# Power_Supply_2.net
KiCad netlist of a schematic drawn in Altium Designer
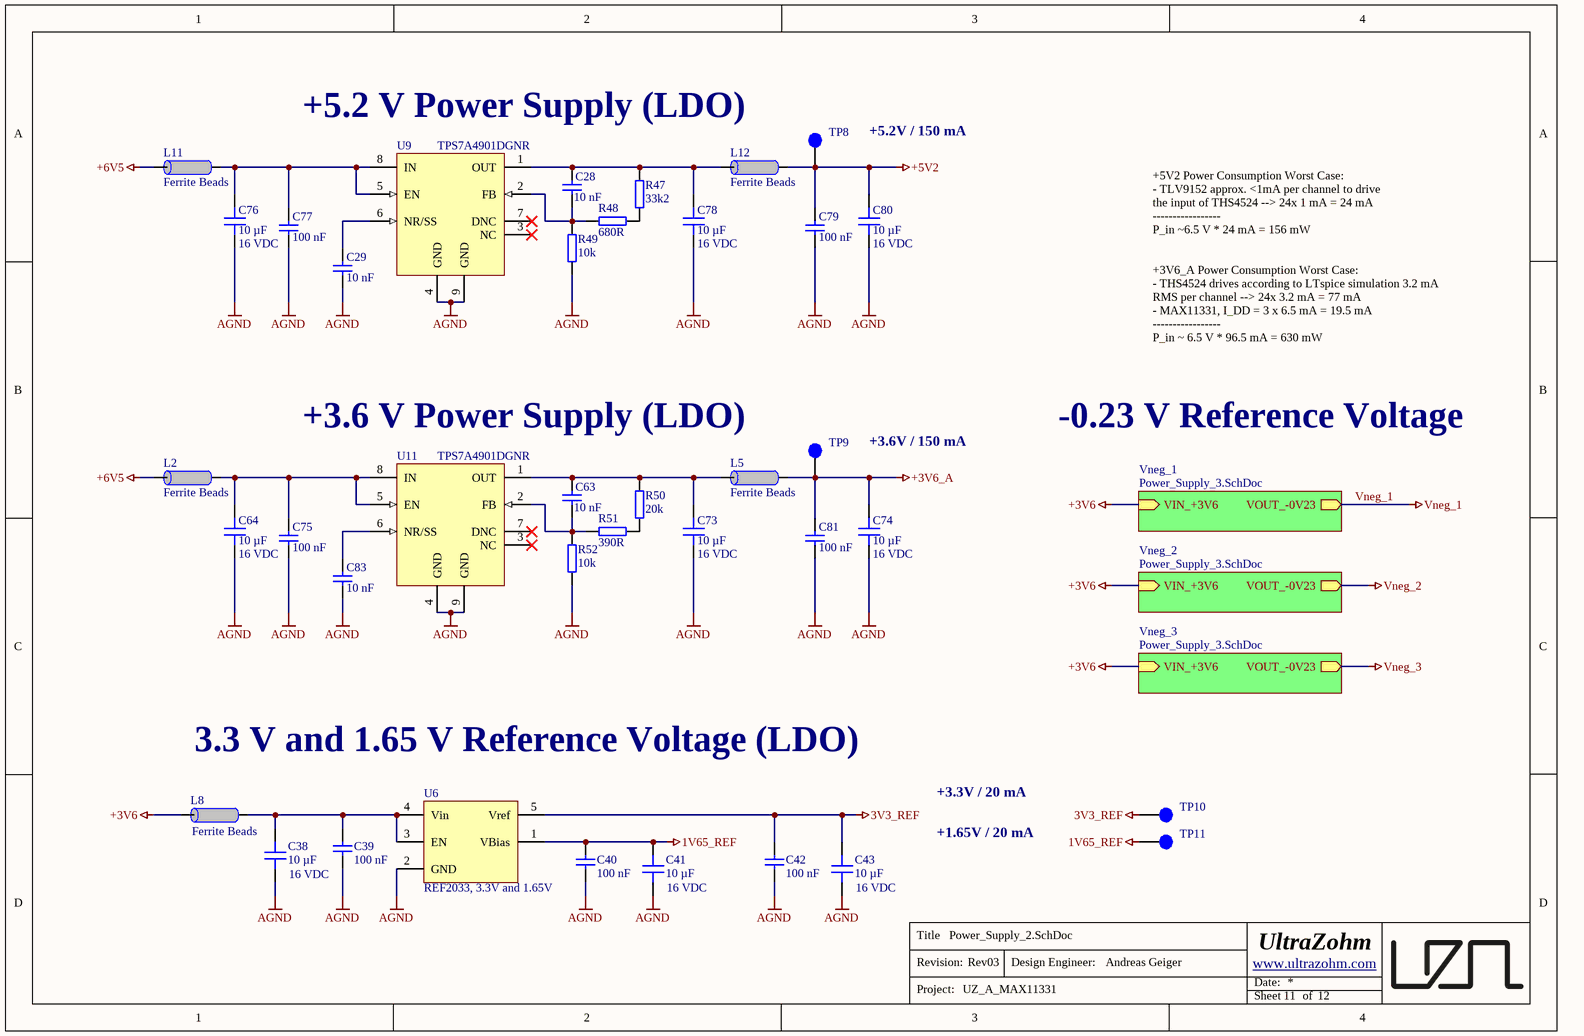
[diagram p0: Power_Supply_2.SchDoc]

(export (version "E")
  (design (tool "Eeschema 10.0.6"))
  (components
    (comp (ref "C28")
      (value "10 nF")
      (footprint "C_0402_TE")
      (description "Generic capacitor")
      (fields
        (field (name "MANUFACTURER PART NUMBER") "UZgen_C_0402_10nF_50V_NP0")
        (field (name "MANUFACTURER") "UZgen")
        (field (name "CREATED FROM") "UZgenTool")
      )
      (libsource (lib "user") (part "CAP-NP"))
    )
    (comp (ref "C29")
      (value "10 nF")
      (footprint "C_0402_TE")
      (description "Generic capacitor")
      (fields
        (field (name "MANUFACTURER PART NUMBER") "UZgen_C_0402_10nF_50V_NP0")
        (field (name "MANUFACTURER") "UZgen")
        (field (name "CREATED FROM") "UZgenTool")
      )
      (libsource (lib "user") (part "CAP-NP"))
    )
    (comp (ref "C38")
      (value "10 µF")
      (footprint "C_0603_TE")
      (description "Capacitor 0603, 16 VDC, 10 µF, X5R")
      (fields
        (field (name "MANUFACTURER PART NUMBER") "CL10A106MO8NQNC")
        (field (name "MANUFACTURER") "Samsung Electro-Mechanics")
        (field (name "VOLTAGE RATING") "16 VDC")
        (field (name "CREATED FROM") "AGeiger")
      )
      (libsource (lib "user") (part "Capacitor"))
    )
    (comp (ref "C39")
      (value "100 nF")
      (footprint "C_0603_TE")
      (description "Generic capacitor")
      (fields
        (field (name "MANUFACTURER PART NUMBER") "UZgen_C_0603_100nF_50V_X7R")
        (field (name "MANUFACTURER") "UZgen")
        (field (name "CREATED FROM") "AGeiger")
      )
      (libsource (lib "user") (part "CAP-NP"))
    )
    (comp (ref "C40")
      (value "100 nF")
      (footprint "C_0603_TE")
      (description "Generic capacitor")
      (fields
        (field (name "MANUFACTURER PART NUMBER") "UZgen_C_0603_100nF_50V_X7R")
        (field (name "MANUFACTURER") "UZgen")
        (field (name "CREATED FROM") "AGeiger")
      )
      (libsource (lib "user") (part "CAP-NP"))
    )
    (comp (ref "C41")
      (value "10 µF")
      (footprint "C_0603_TE")
      (description "Capacitor 0603, 16 VDC, 10 µF, X5R")
      (fields
        (field (name "MANUFACTURER PART NUMBER") "CL10A106MO8NQNC")
        (field (name "MANUFACTURER") "Samsung Electro-Mechanics")
        (field (name "VOLTAGE RATING") "16 VDC")
        (field (name "CREATED FROM") "AGeiger")
      )
      (libsource (lib "user") (part "Capacitor"))
    )
    (comp (ref "C42")
      (value "100 nF")
      (footprint "C_0603_TE")
      (description "Generic capacitor")
      (fields
        (field (name "MANUFACTURER PART NUMBER") "UZgen_C_0603_100nF_50V_X7R")
        (field (name "MANUFACTURER") "UZgen")
        (field (name "CREATED FROM") "AGeiger")
      )
      (libsource (lib "user") (part "CAP-NP"))
    )
    (comp (ref "C43")
      (value "10 µF")
      (footprint "C_0603_TE")
      (description "Capacitor 0603, 16 VDC, 10 µF, X5R")
      (fields
        (field (name "MANUFACTURER PART NUMBER") "CL10A106MO8NQNC")
        (field (name "MANUFACTURER") "Samsung Electro-Mechanics")
        (field (name "VOLTAGE RATING") "16 VDC")
        (field (name "CREATED FROM") "AGeiger")
      )
      (libsource (lib "user") (part "Capacitor"))
    )
    (comp (ref "C63")
      (value "10 nF")
      (footprint "C_0402_TE")
      (description "Generic capacitor")
      (fields
        (field (name "MANUFACTURER PART NUMBER") "UZgen_C_0402_10nF_50V_NP0")
        (field (name "MANUFACTURER") "UZgen")
        (field (name "CREATED FROM") "UZgenTool")
      )
      (libsource (lib "user") (part "CAP-NP"))
    )
    (comp (ref "C64")
      (value "10 µF")
      (footprint "C_0603_TE")
      (description "Capacitor 0603, 16 VDC, 10 µF, X5R")
      (fields
        (field (name "MANUFACTURER PART NUMBER") "CL10A106MO8NQNC")
        (field (name "MANUFACTURER") "Samsung Electro-Mechanics")
        (field (name "VOLTAGE RATING") "16 VDC")
        (field (name "CREATED FROM") "AGeiger")
      )
      (libsource (lib "user") (part "Capacitor"))
    )
    (comp (ref "C73")
      (value "10 µF")
      (footprint "C_0603_TE")
      (description "Capacitor 0603, 16 VDC, 10 µF, X5R")
      (fields
        (field (name "MANUFACTURER PART NUMBER") "CL10A106MO8NQNC")
        (field (name "MANUFACTURER") "Samsung Electro-Mechanics")
        (field (name "VOLTAGE RATING") "16 VDC")
        (field (name "CREATED FROM") "AGeiger")
      )
      (libsource (lib "user") (part "Capacitor"))
    )
    (comp (ref "C74")
      (value "10 µF")
      (footprint "C_0603_TE")
      (description "Capacitor 0603, 16 VDC, 10 µF, X5R")
      (fields
        (field (name "MANUFACTURER PART NUMBER") "CL10A106MO8NQNC")
        (field (name "MANUFACTURER") "Samsung Electro-Mechanics")
        (field (name "VOLTAGE RATING") "16 VDC")
        (field (name "CREATED FROM") "AGeiger")
      )
      (libsource (lib "user") (part "Capacitor"))
    )
    (comp (ref "C75")
      (value "100 nF")
      (footprint "C_0603_TE")
      (description "Generic capacitor")
      (fields
        (field (name "MANUFACTURER PART NUMBER") "UZgen_C_0603_100nF_50V_X7R")
        (field (name "MANUFACTURER") "UZgen")
        (field (name "CREATED FROM") "AGeiger")
      )
      (libsource (lib "user") (part "CAP-NP"))
    )
    (comp (ref "C76")
      (value "10 µF")
      (footprint "C_0603_TE")
      (description "Capacitor 0603, 16 VDC, 10 µF, X5R")
      (fields
        (field (name "MANUFACTURER PART NUMBER") "CL10A106MO8NQNC")
        (field (name "MANUFACTURER") "Samsung Electro-Mechanics")
        (field (name "VOLTAGE RATING") "16 VDC")
        (field (name "CREATED FROM") "AGeiger")
      )
      (libsource (lib "user") (part "Capacitor"))
    )
    (comp (ref "C77")
      (value "100 nF")
      (footprint "C_0603_TE")
      (description "Generic capacitor")
      (fields
        (field (name "MANUFACTURER PART NUMBER") "UZgen_C_0603_100nF_50V_X7R")
        (field (name "MANUFACTURER") "UZgen")
        (field (name "CREATED FROM") "AGeiger")
      )
      (libsource (lib "user") (part "CAP-NP"))
    )
    (comp (ref "C78")
      (value "10 µF")
      (footprint "C_0603_TE")
      (description "Capacitor 0603, 16 VDC, 10 µF, X5R")
      (fields
        (field (name "MANUFACTURER PART NUMBER") "CL10A106MO8NQNC")
        (field (name "MANUFACTURER") "Samsung Electro-Mechanics")
        (field (name "VOLTAGE RATING") "16 VDC")
        (field (name "CREATED FROM") "AGeiger")
      )
      (libsource (lib "user") (part "Capacitor"))
    )
    (comp (ref "C79")
      (value "100 nF")
      (footprint "C_0603_TE")
      (description "Generic capacitor")
      (fields
        (field (name "MANUFACTURER PART NUMBER") "UZgen_C_0603_100nF_50V_X7R")
        (field (name "MANUFACTURER") "UZgen")
        (field (name "CREATED FROM") "AGeiger")
      )
      (libsource (lib "user") (part "CAP-NP"))
    )
    (comp (ref "C80")
      (value "10 µF")
      (footprint "C_0603_TE")
      (description "Capacitor 0603, 16 VDC, 10 µF, X5R")
      (fields
        (field (name "MANUFACTURER PART NUMBER") "CL10A106MO8NQNC")
        (field (name "MANUFACTURER") "Samsung Electro-Mechanics")
        (field (name "VOLTAGE RATING") "16 VDC")
        (field (name "CREATED FROM") "AGeiger")
      )
      (libsource (lib "user") (part "Capacitor"))
    )
    (comp (ref "C81")
      (value "100 nF")
      (footprint "C_0603_TE")
      (description "Generic capacitor")
      (fields
        (field (name "MANUFACTURER PART NUMBER") "UZgen_C_0603_100nF_50V_X7R")
        (field (name "MANUFACTURER") "UZgen")
        (field (name "CREATED FROM") "AGeiger")
      )
      (libsource (lib "user") (part "CAP-NP"))
    )
    (comp (ref "C83")
      (value "10 nF")
      (footprint "C_0402_TE")
      (description "Generic capacitor")
      (fields
        (field (name "MANUFACTURER PART NUMBER") "UZgen_C_0402_10nF_50V_NP0")
        (field (name "MANUFACTURER") "UZgen")
        (field (name "CREATED FROM") "UZgenTool")
      )
      (libsource (lib "user") (part "CAP-NP"))
    )
    (comp (ref "L2")
      (value "UPZ2012E601-2R0TF")
      (footprint "INDC2012X92N_V")
      (description "2A 1 90mΩ 600Ω@100MHz ±25% 0805  Ferrite Beads ROHS")
      (fields
        (field (name "COMPONENT TYPE") "Ferrite Beads")
        (field (name "MANUFACTURER") "Sunlord")
        (field (name "LCSC PART NUMBER") "C98308")
        (field (name "CREATED FROM") "AGeiger")
      )
      (libsource (lib "user") (part "Ferrite_Bead"))
    )
    (comp (ref "L5")
      (value "UPZ2012E601-2R0TF")
      (footprint "INDC2012X92N_V")
      (description "2A 1 90mΩ 600Ω@100MHz ±25% 0805  Ferrite Beads ROHS")
      (fields
        (field (name "COMPONENT TYPE") "Ferrite Beads")
        (field (name "MANUFACTURER") "Sunlord")
        (field (name "LCSC PART NUMBER") "C98308")
        (field (name "CREATED FROM") "AGeiger")
      )
      (libsource (lib "user") (part "Ferrite_Bead"))
    )
    (comp (ref "L8")
      (value "UPZ2012E601-2R0TF")
      (footprint "INDC2012X92N_V")
      (description "2A 1 90mΩ 600Ω@100MHz ±25% 0805  Ferrite Beads ROHS")
      (fields
        (field (name "COMPONENT TYPE") "Ferrite Beads")
        (field (name "MANUFACTURER") "Sunlord")
        (field (name "LCSC PART NUMBER") "C98308")
        (field (name "CREATED FROM") "AGeiger")
      )
      (libsource (lib "user") (part "Ferrite_Bead"))
    )
    (comp (ref "L11")
      (value "UPZ2012E601-2R0TF")
      (footprint "INDC2012X92N_V")
      (description "2A 1 90mΩ 600Ω@100MHz ±25% 0805  Ferrite Beads ROHS")
      (fields
        (field (name "COMPONENT TYPE") "Ferrite Beads")
        (field (name "MANUFACTURER") "Sunlord")
        (field (name "LCSC PART NUMBER") "C98308")
        (field (name "CREATED FROM") "AGeiger")
      )
      (libsource (lib "user") (part "Ferrite_Bead"))
    )
    (comp (ref "L12")
      (value "UPZ2012E601-2R0TF")
      (footprint "INDC2012X92N_V")
      (description "2A 1 90mΩ 600Ω@100MHz ±25% 0805  Ferrite Beads ROHS")
      (fields
        (field (name "COMPONENT TYPE") "Ferrite Beads")
        (field (name "MANUFACTURER") "Sunlord")
        (field (name "LCSC PART NUMBER") "C98308")
        (field (name "CREATED FROM") "AGeiger")
      )
      (libsource (lib "user") (part "Ferrite_Bead"))
    )
    (comp (ref "R47")
      (value "33k2")
      (footprint "R_0402_TE")
      (description "62.5mW Thick Film Resistor 50V ±100ppm/℃ ±1% 33.2kΩ 0402 Chip Resistor - Surface Mount ROHS")
      (fields
        (field (name "TOLERANCE") "1%")
        (field (name "MANUFACTURER PART NUMBER") "0402WGF3322TCE")
        (field (name "CREATED FROM") "AGeiger")
      )
      (libsource (lib "user") (part "Resistor"))
    )
    (comp (ref "R48")
      (value "680R")
      (footprint "R_0402_TE")
      (description "Generic resistor")
      (fields
        (field (name "MANUFACTURER PART NUMBER") "UZgen_R_0402_680R")
        (field (name "MANUFACTURER") "UZgen")
        (field (name "CREATED FROM") "UZgenTool")
      )
      (libsource (lib "user") (part "RES"))
    )
    (comp (ref "R49")
      (value "10k")
      (footprint "R_0402_TE")
      (description "Generic resistor")
      (fields
        (field (name "MANUFACTURER PART NUMBER") "UZgen_R_0402_10k")
        (field (name "MANUFACTURER") "UZgen")
        (field (name "CREATED FROM") "UZgenTool")
      )
      (libsource (lib "user") (part "RES"))
    )
    (comp (ref "R50")
      (value "20k")
      (footprint "R_0402_TE")
      (description "Generic resistor")
      (fields
        (field (name "TOLERANCE") "1 %")
        (field (name "MANUFACTURER PART NUMBER") "UZgen_R_0402_20k")
        (field (name "CREATED FROM") "UZgenTool")
      )
      (libsource (lib "user") (part "RES"))
    )
    (comp (ref "R51")
      (value "390R")
      (footprint "R_0402_TE")
      (description "Generic resistor")
      (fields
        (field (name "MANUFACTURER PART NUMBER") "UZgen_R_0402_390R")
        (field (name "MANUFACTURER") "UZgen")
        (field (name "CREATED FROM") "UZgenTool")
      )
      (libsource (lib "user") (part "RES"))
    )
    (comp (ref "R52")
      (value "10k")
      (footprint "R_0402_TE")
      (description "Generic resistor")
      (fields
        (field (name "MANUFACTURER PART NUMBER") "UZgen_R_0402_10k")
        (field (name "MANUFACTURER") "UZgen")
        (field (name "CREATED FROM") "UZgenTool")
      )
      (libsource (lib "user") (part "RES"))
    )
    (comp (ref "TP8")
      (value "Testpoint 1mm")
      (footprint "TP_1mm")
      (fields
        (field (name "MANUFACTURER PART NUMBER") "Testpoint_1mm")
        (field (name "MANUFACTURER") "UltraZohm")
        (field (name "CREATED") "2018_06_25_AGeiger")
        (field (name "CREATED FROM") "AGeiger")
      )
      (libsource (lib "user") (part "TP_1mm"))
    )
    (comp (ref "TP9")
      (value "Testpoint 1mm")
      (footprint "TP_1mm")
      (fields
        (field (name "MANUFACTURER PART NUMBER") "Testpoint_1mm")
        (field (name "MANUFACTURER") "UltraZohm")
        (field (name "CREATED") "2018_06_25_AGeiger")
        (field (name "CREATED FROM") "AGeiger")
      )
      (libsource (lib "user") (part "TP_1mm"))
    )
    (comp (ref "TP10")
      (value "Testpoint 1mm")
      (footprint "TP_1mm")
      (fields
        (field (name "MANUFACTURER PART NUMBER") "Testpoint_1mm")
        (field (name "MANUFACTURER") "UltraZohm")
        (field (name "CREATED") "2018_06_25_AGeiger")
        (field (name "CREATED FROM") "AGeiger")
      )
      (libsource (lib "user") (part "TP_1mm"))
    )
    (comp (ref "TP11")
      (value "Testpoint 1mm")
      (footprint "TP_1mm")
      (fields
        (field (name "MANUFACTURER PART NUMBER") "Testpoint_1mm")
        (field (name "MANUFACTURER") "UltraZohm")
        (field (name "CREATED") "2018_06_25_AGeiger")
        (field (name "CREATED FROM") "AGeiger")
      )
      (libsource (lib "user") (part "TP_1mm"))
    )
    (comp (ref "U6")
      (value "REF2033, 3.3V and 1.65V")
      (footprint "SOT23-5_N")
      (description "REF20xx Low-Drift, Low-Power, Dual-Output, VREF and VREF / 2 Voltage References")
      (fields
        (field (name "MANUFACTURER PART NUMBER") "REF2033AIDDCT")
        (field (name "MANUFACTURER") "Texas Instruments")
        (field (name "CREATED FROM") "AGeiger")
      )
      (libsource (lib "user") (part "REF2033"))
    )
    (comp (ref "U9")
      (value "TPS7A4901DGNR")
      (footprint "SOP65P490X110-9N")
      (description "36 V, -150 mA, ultralow-noise, positive linear regulator")
      (fields
        (field (name "MANUFACTURER") "Texas Instruments")
        (field (name "LCSC PART NUMBER") "C16430")
        (field (name "CREATED FROM") "AGeiger")
      )
      (libsource (lib "user") (part "TPS7A4901"))
    )
    (comp (ref "U11")
      (value "TPS7A4901DGNR")
      (footprint "SOP65P490X110-9N")
      (description "36 V, -150 mA, ultralow-noise, positive linear regulator")
      (fields
        (field (name "MANUFACTURER") "Texas Instruments")
        (field (name "LCSC PART NUMBER") "C16430")
        (field (name "CREATED FROM") "AGeiger")
      )
      (libsource (lib "user") (part "TPS7A4901"))
    )
  )
  (nets
    (net (code "1") (name "+3V6") (class "Default")
      (node (ref "L8") (pin "2") (pinfunction "2_2") (pintype "passive"))
    )
    (net (code "2") (name "+3V6_A") (class "Default")
      (node (ref "C74") (pin "2") (pinfunction "2_2") (pintype "passive"))
      (node (ref "C81") (pin "2") (pinfunction "2_2") (pintype "passive"))
      (node (ref "L5") (pin "1") (pinfunction "1_1") (pintype "passive"))
      (node (ref "TP9") (pin "1") (pintype "passive"))
    )
    (net (code "3") (name "+5V2") (class "Default")
      (node (ref "C79") (pin "2") (pinfunction "2_2") (pintype "passive"))
      (node (ref "C80") (pin "2") (pinfunction "2_2") (pintype "passive"))
      (node (ref "L12") (pin "1") (pinfunction "1_1") (pintype "passive"))
      (node (ref "TP8") (pin "1") (pintype "passive"))
    )
    (net (code "4") (name "+6V5") (class "Default")
      (node (ref "L11") (pin "2") (pinfunction "2_2") (pintype "passive"))
      (node (ref "L2") (pin "2") (pinfunction "2_2") (pintype "passive"))
    )
    (net (code "5") (name "1V65_REF") (class "Default")
      (node (ref "C40") (pin "2") (pinfunction "2_2") (pintype "passive"))
      (node (ref "C41") (pin "2") (pinfunction "2_2") (pintype "passive"))
      (node (ref "TP11") (pin "1") (pintype "passive"))
      (node (ref "U6") (pin "1") (pinfunction "VBias_1") (pintype "passive"))
    )
    (net (code "6") (name "3V3_REF") (class "Default")
      (node (ref "C42") (pin "2") (pinfunction "2_2") (pintype "passive"))
      (node (ref "C43") (pin "2") (pinfunction "2_2") (pintype "passive"))
      (node (ref "TP10") (pin "1") (pintype "passive"))
      (node (ref "U6") (pin "5") (pinfunction "Vref_5") (pintype "passive"))
    )
    (net (code "7") (name "AGND") (class "Default")
      (node (ref "C29") (pin "1") (pinfunction "1_1") (pintype "passive"))
      (node (ref "C38") (pin "1") (pinfunction "1_1") (pintype "passive"))
      (node (ref "C39") (pin "1") (pinfunction "1_1") (pintype "passive"))
      (node (ref "C40") (pin "1") (pinfunction "1_1") (pintype "passive"))
      (node (ref "C41") (pin "1") (pinfunction "1_1") (pintype "passive"))
      (node (ref "C42") (pin "1") (pinfunction "1_1") (pintype "passive"))
      (node (ref "C43") (pin "1") (pinfunction "1_1") (pintype "passive"))
      (node (ref "C64") (pin "1") (pinfunction "1_1") (pintype "passive"))
      (node (ref "C73") (pin "1") (pinfunction "1_1") (pintype "passive"))
      (node (ref "C74") (pin "1") (pinfunction "1_1") (pintype "passive"))
      (node (ref "C75") (pin "1") (pinfunction "1_1") (pintype "passive"))
      (node (ref "C76") (pin "1") (pinfunction "1_1") (pintype "passive"))
      (node (ref "C77") (pin "1") (pinfunction "1_1") (pintype "passive"))
      (node (ref "C78") (pin "1") (pinfunction "1_1") (pintype "passive"))
      (node (ref "C79") (pin "1") (pinfunction "1_1") (pintype "passive"))
      (node (ref "C80") (pin "1") (pinfunction "1_1") (pintype "passive"))
      (node (ref "C81") (pin "1") (pinfunction "1_1") (pintype "passive"))
      (node (ref "C83") (pin "1") (pinfunction "1_1") (pintype "passive"))
      (node (ref "R49") (pin "1") (pinfunction "1_1") (pintype "passive"))
      (node (ref "R52") (pin "1") (pinfunction "1_1") (pintype "passive"))
      (node (ref "U11") (pin "4") (pinfunction "GND_4") (pintype "power_in"))
      (node (ref "U11") (pin "9") (pinfunction "GND_9") (pintype "power_in"))
      (node (ref "U6") (pin "2") (pinfunction "GND_2") (pintype "passive"))
      (node (ref "U9") (pin "4") (pinfunction "GND_4") (pintype "power_in"))
      (node (ref "U9") (pin "9") (pinfunction "GND_9") (pintype "power_in"))
    )
    (net (code "8") (name "Net-(R47-Pad1)") (class "Default")
      (node (ref "R47") (pin "1") (pinfunction "1_1") (pintype "passive"))
      (node (ref "R48") (pin "2") (pinfunction "2_2") (pintype "passive"))
    )
    (net (code "9") (name "Net-(R50-Pad1)") (class "Default")
      (node (ref "R50") (pin "1") (pinfunction "1_1") (pintype "passive"))
      (node (ref "R51") (pin "2") (pinfunction "2_2") (pintype "passive"))
    )
    (net (code "10") (name "Net-(U6-EN)") (class "Default")
      (node (ref "C38") (pin "2") (pinfunction "2_2") (pintype "passive"))
      (node (ref "C39") (pin "2") (pinfunction "2_2") (pintype "passive"))
      (node (ref "L8") (pin "1") (pinfunction "1_1") (pintype "passive"))
      (node (ref "U6") (pin "3") (pinfunction "EN_3") (pintype "passive"))
      (node (ref "U6") (pin "4") (pinfunction "Vin_4") (pintype "passive"))
    )
    (net (code "11") (name "Net-(U9-EN)") (class "Default")
      (node (ref "C76") (pin "2") (pinfunction "2_2") (pintype "passive"))
      (node (ref "C77") (pin "2") (pinfunction "2_2") (pintype "passive"))
      (node (ref "L11") (pin "1") (pinfunction "1_1") (pintype "passive"))
      (node (ref "U9") (pin "5") (pinfunction "EN_5") (pintype "input"))
      (node (ref "U9") (pin "8") (pinfunction "IN_8") (pintype "power_in"))
    )
    (net (code "12") (name "Net-(U9-FB)") (class "Default")
      (node (ref "C28") (pin "1") (pinfunction "1_1") (pintype "passive"))
      (node (ref "R48") (pin "1") (pinfunction "1_1") (pintype "passive"))
      (node (ref "R49") (pin "2") (pinfunction "2_2") (pintype "passive"))
      (node (ref "U9") (pin "2") (pinfunction "FB_2") (pintype "input"))
    )
    (net (code "13") (name "Net-(U9-NR{slash}SS)") (class "Default")
      (node (ref "C29") (pin "2") (pinfunction "2_2") (pintype "passive"))
      (node (ref "U9") (pin "6") (pinfunction "NR/SS_6") (pintype "input"))
    )
    (net (code "14") (name "Net-(U9-OUT)") (class "Default")
      (node (ref "C28") (pin "2") (pinfunction "2_2") (pintype "passive"))
      (node (ref "C78") (pin "2") (pinfunction "2_2") (pintype "passive"))
      (node (ref "L12") (pin "2") (pinfunction "2_2") (pintype "passive"))
      (node (ref "R47") (pin "2") (pinfunction "2_2") (pintype "passive"))
      (node (ref "U9") (pin "1") (pinfunction "OUT_1") (pintype "power_in"))
    )
    (net (code "15") (name "Net-(U11-EN)") (class "Default")
      (node (ref "C64") (pin "2") (pinfunction "2_2") (pintype "passive"))
      (node (ref "C75") (pin "2") (pinfunction "2_2") (pintype "passive"))
      (node (ref "L2") (pin "1") (pinfunction "1_1") (pintype "passive"))
      (node (ref "U11") (pin "5") (pinfunction "EN_5") (pintype "input"))
      (node (ref "U11") (pin "8") (pinfunction "IN_8") (pintype "power_in"))
    )
    (net (code "16") (name "Net-(U11-FB)") (class "Default")
      (node (ref "C63") (pin "1") (pinfunction "1_1") (pintype "passive"))
      (node (ref "R51") (pin "1") (pinfunction "1_1") (pintype "passive"))
      (node (ref "R52") (pin "2") (pinfunction "2_2") (pintype "passive"))
      (node (ref "U11") (pin "2") (pinfunction "FB_2") (pintype "input"))
    )
    (net (code "17") (name "Net-(U11-NR{slash}SS)") (class "Default")
      (node (ref "C83") (pin "2") (pinfunction "2_2") (pintype "passive"))
      (node (ref "U11") (pin "6") (pinfunction "NR/SS_6") (pintype "input"))
    )
    (net (code "18") (name "Net-(U11-OUT)") (class "Default")
      (node (ref "C63") (pin "2") (pinfunction "2_2") (pintype "passive"))
      (node (ref "C73") (pin "2") (pinfunction "2_2") (pintype "passive"))
      (node (ref "L5") (pin "2") (pinfunction "2_2") (pintype "passive"))
      (node (ref "R50") (pin "2") (pinfunction "2_2") (pintype "passive"))
      (node (ref "U11") (pin "1") (pinfunction "OUT_1") (pintype "power_in"))
    )
    (net (code "22") (name "unconnected-(U9-DNC-Pad7)") (class "Default")
      (node (ref "U9") (pin "7") (pinfunction "DNC_7") (pintype "passive+no_connect"))
    )
    (net (code "23") (name "unconnected-(U9-NC-Pad3)") (class "Default")
      (node (ref "U9") (pin "3") (pinfunction "NC_3") (pintype "passive+no_connect"))
    )
    (net (code "24") (name "unconnected-(U11-DNC-Pad7)") (class "Default")
      (node (ref "U11") (pin "7") (pinfunction "DNC_7") (pintype "passive+no_connect"))
    )
    (net (code "25") (name "unconnected-(U11-NC-Pad3)") (class "Default")
      (node (ref "U11") (pin "3") (pinfunction "NC_3") (pintype "passive+no_connect"))
    )
  )
)
